# switcher.net
KiCad netlist of a schematic drawn in Altium Designer
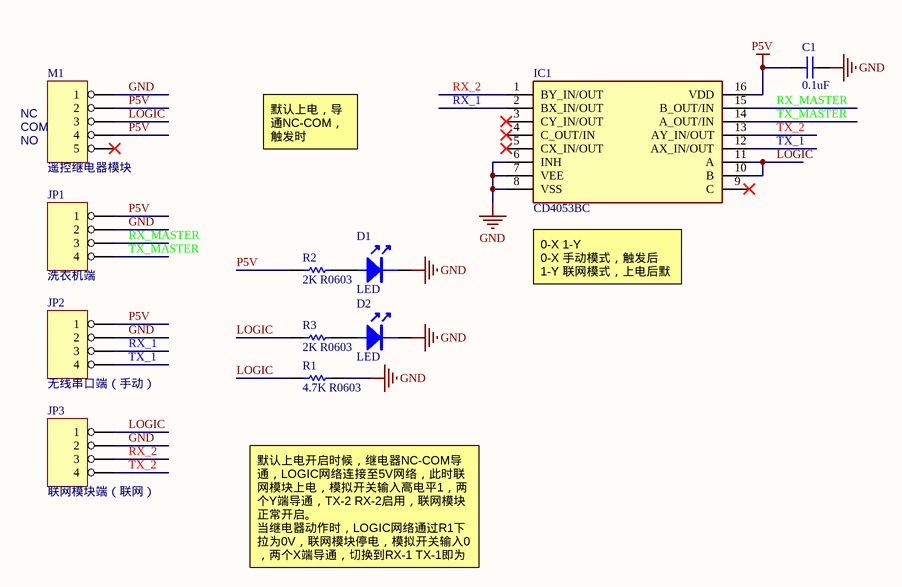
[diagram p0: switcher.SchDoc]

(export (version "E")
  (design (tool "Eeschema 10.0.6"))
  (components
    (comp (ref "C1")
      (value "0.1uF")
      (footprint "0603_C")
      (description "Capacitor")
      (fields (field (name "PUBLISHER") "Altium Limited"))
      (libsource (lib "My Footprint") (part "CAP"))
    )
    (comp (ref "D1")
      (value "LED")
      (footprint "0603_LED")
      (description "LED 发光二极管")
      (libsource (lib "My Footprint") (part "LED"))
    )
    (comp (ref "D2")
      (value "LED")
      (footprint "0603_LED")
      (description "LED 发光二极管")
      (libsource (lib "My Footprint") (part "LED"))
    )
    (comp (ref "IC1")
      (value "CD4053BC")
      (footprint "SOIC-16")
      (description "Integrated Circuit")
      (libsource (lib "SamacSys") (part "CD4053BC"))
    )
    (comp (ref "JP1") (value "洗衣机端") (footprint "header4") (libsource (lib "My Footprint") (part "HEADER 4")))
    (comp (ref "JP2")
      (value "无线串口端（手动）")
      (footprint "header4")
      (libsource (lib "My Footprint") (part "HEADER 4"))
    )
    (comp (ref "JP3")
      (value "联网模块端（联网）")
      (footprint "header4")
      (libsource (lib "My Footprint") (part "HEADER 4"))
    )
    (comp (ref "M1")
      (value "遥控继电器模块")
      (footprint "header5")
      (libsource (lib "My Footprint") (part "HEADER 5"))
    )
    (comp (ref "R1")
      (value "4.7K R0603")
      (footprint "0603_R")
      (description "Resistor")
      (fields (field (name "PUBLISHER") "Altium Limited"))
      (libsource (lib "My Footprint") (part "RES"))
    )
    (comp (ref "R2")
      (value "2K R0603")
      (footprint "0603_R")
      (description "Resistor")
      (fields (field (name "PUBLISHER") "Altium Limited"))
      (libsource (lib "My Footprint") (part "RES"))
    )
    (comp (ref "R3")
      (value "2K R0603")
      (footprint "0603_R")
      (description "Resistor")
      (fields (field (name "PUBLISHER") "Altium Limited"))
      (libsource (lib "My Footprint") (part "RES"))
    )
  )
  (nets
    (net (code "1") (name "/LOGIC") (class "Default")
      (node (ref "IC1") (pin "10") (pinfunction "B_10") (pintype "passive"))
      (node (ref "IC1") (pin "11") (pinfunction "A_11") (pintype "passive"))
      (node (ref "JP3") (pin "1") (pinfunction "1_1") (pintype "passive"))
      (node (ref "M1") (pin "3") (pinfunction "3_3") (pintype "passive"))
      (node (ref "R1") (pin "2") (pinfunction "2_2") (pintype "passive"))
      (node (ref "R3") (pin "1") (pinfunction "1_1") (pintype "passive"))
    )
    (net (code "2") (name "/RX_1") (class "Default")
      (node (ref "IC1") (pin "2") (pinfunction "BX_IN/OUT_2") (pintype "passive"))
      (node (ref "JP2") (pin "3") (pinfunction "3_3") (pintype "passive"))
    )
    (net (code "3") (name "/RX_2") (class "Default")
      (node (ref "IC1") (pin "1") (pinfunction "BY_IN/OUT_1") (pintype "passive"))
      (node (ref "JP3") (pin "3") (pinfunction "3_3") (pintype "passive"))
    )
    (net (code "4") (name "/RX_MASTER") (class "Default")
      (node (ref "IC1") (pin "15") (pinfunction "B_OUT/IN_15") (pintype "passive"))
      (node (ref "JP1") (pin "3") (pinfunction "3_3") (pintype "passive"))
    )
    (net (code "5") (name "/TX_1") (class "Default")
      (node (ref "IC1") (pin "12") (pinfunction "AX_IN/OUT_12") (pintype "passive"))
      (node (ref "JP2") (pin "4") (pinfunction "4_4") (pintype "passive"))
    )
    (net (code "6") (name "/TX_2") (class "Default")
      (node (ref "IC1") (pin "13") (pinfunction "AY_IN/OUT_13") (pintype "passive"))
      (node (ref "JP3") (pin "4") (pinfunction "4_4") (pintype "passive"))
    )
    (net (code "7") (name "/TX_MASTER") (class "Default")
      (node (ref "IC1") (pin "14") (pinfunction "A_OUT/IN_14") (pintype "passive"))
      (node (ref "JP1") (pin "4") (pinfunction "4_4") (pintype "passive"))
    )
    (net (code "8") (name "GND") (class "Default")
      (node (ref "C1") (pin "2") (pinfunction "2_2") (pintype "passive"))
      (node (ref "D1") (pin "2") (pinfunction "K_2") (pintype "passive"))
      (node (ref "D2") (pin "2") (pinfunction "K_2") (pintype "passive"))
      (node (ref "IC1") (pin "6") (pinfunction "INH_6") (pintype "passive"))
      (node (ref "IC1") (pin "7") (pinfunction "VEE_7") (pintype "passive"))
      (node (ref "IC1") (pin "8") (pinfunction "VSS_8") (pintype "passive"))
      (node (ref "JP1") (pin "2") (pinfunction "2_2") (pintype "passive"))
      (node (ref "JP2") (pin "2") (pinfunction "2_2") (pintype "passive"))
      (node (ref "JP3") (pin "2") (pinfunction "2_2") (pintype "passive"))
      (node (ref "M1") (pin "1") (pinfunction "1_1") (pintype "passive"))
      (node (ref "R1") (pin "1") (pinfunction "1_1") (pintype "passive"))
    )
    (net (code "9") (name "Net-(D1-A)") (class "Default")
      (node (ref "D1") (pin "1") (pinfunction "A_1") (pintype "passive"))
      (node (ref "R2") (pin "2") (pinfunction "2_2") (pintype "passive"))
    )
    (net (code "10") (name "Net-(D2-A)") (class "Default")
      (node (ref "D2") (pin "1") (pinfunction "A_1") (pintype "passive"))
      (node (ref "R3") (pin "2") (pinfunction "2_2") (pintype "passive"))
    )
    (net (code "11") (name "P5V") (class "Default")
      (node (ref "C1") (pin "1") (pinfunction "1_1") (pintype "passive"))
      (node (ref "IC1") (pin "16") (pinfunction "VDD_16") (pintype "passive"))
      (node (ref "JP1") (pin "1") (pinfunction "1_1") (pintype "passive"))
      (node (ref "JP2") (pin "1") (pinfunction "1_1") (pintype "passive"))
      (node (ref "M1") (pin "2") (pinfunction "2_2") (pintype "passive"))
      (node (ref "M1") (pin "4") (pinfunction "4_4") (pintype "passive"))
      (node (ref "R2") (pin "1") (pinfunction "1_1") (pintype "passive"))
    )
    (net (code "12") (name "unconnected-(IC1-C-Pad9)") (class "Default")
      (node (ref "IC1") (pin "9") (pinfunction "C_9") (pintype "passive+no_connect"))
    )
    (net (code "13") (name "unconnected-(IC1-CX_IN{slash}OUT-Pad5)") (class "Default")
      (node (ref "IC1") (pin "5") (pinfunction "CX_IN/OUT_5") (pintype "passive+no_connect"))
    )
    (net (code "14") (name "unconnected-(IC1-CY_IN{slash}OUT-Pad3)") (class "Default")
      (node (ref "IC1") (pin "3") (pinfunction "CY_IN/OUT_3") (pintype "passive+no_connect"))
    )
    (net (code "15") (name "unconnected-(IC1-C_OUT{slash}IN-Pad4)") (class "Default")
      (node (ref "IC1") (pin "4") (pinfunction "C_OUT/IN_4") (pintype "passive+no_connect"))
    )
    (net (code "16") (name "unconnected-(M1-Pad5)") (class "Default")
      (node (ref "M1") (pin "5") (pinfunction "5_5") (pintype "passive+no_connect"))
    )
  )
)
